# BEP32.net
KiCad netlist of a schematic drawn in EAGLE
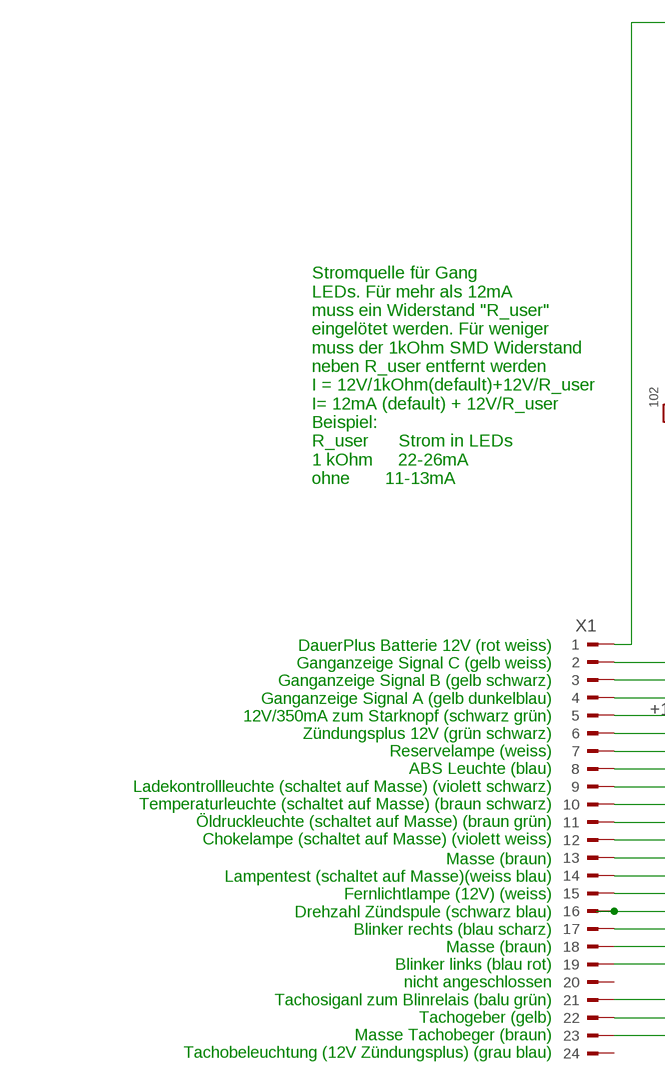
[diagram p0: schematic, sheet 1, part 1 of 2]
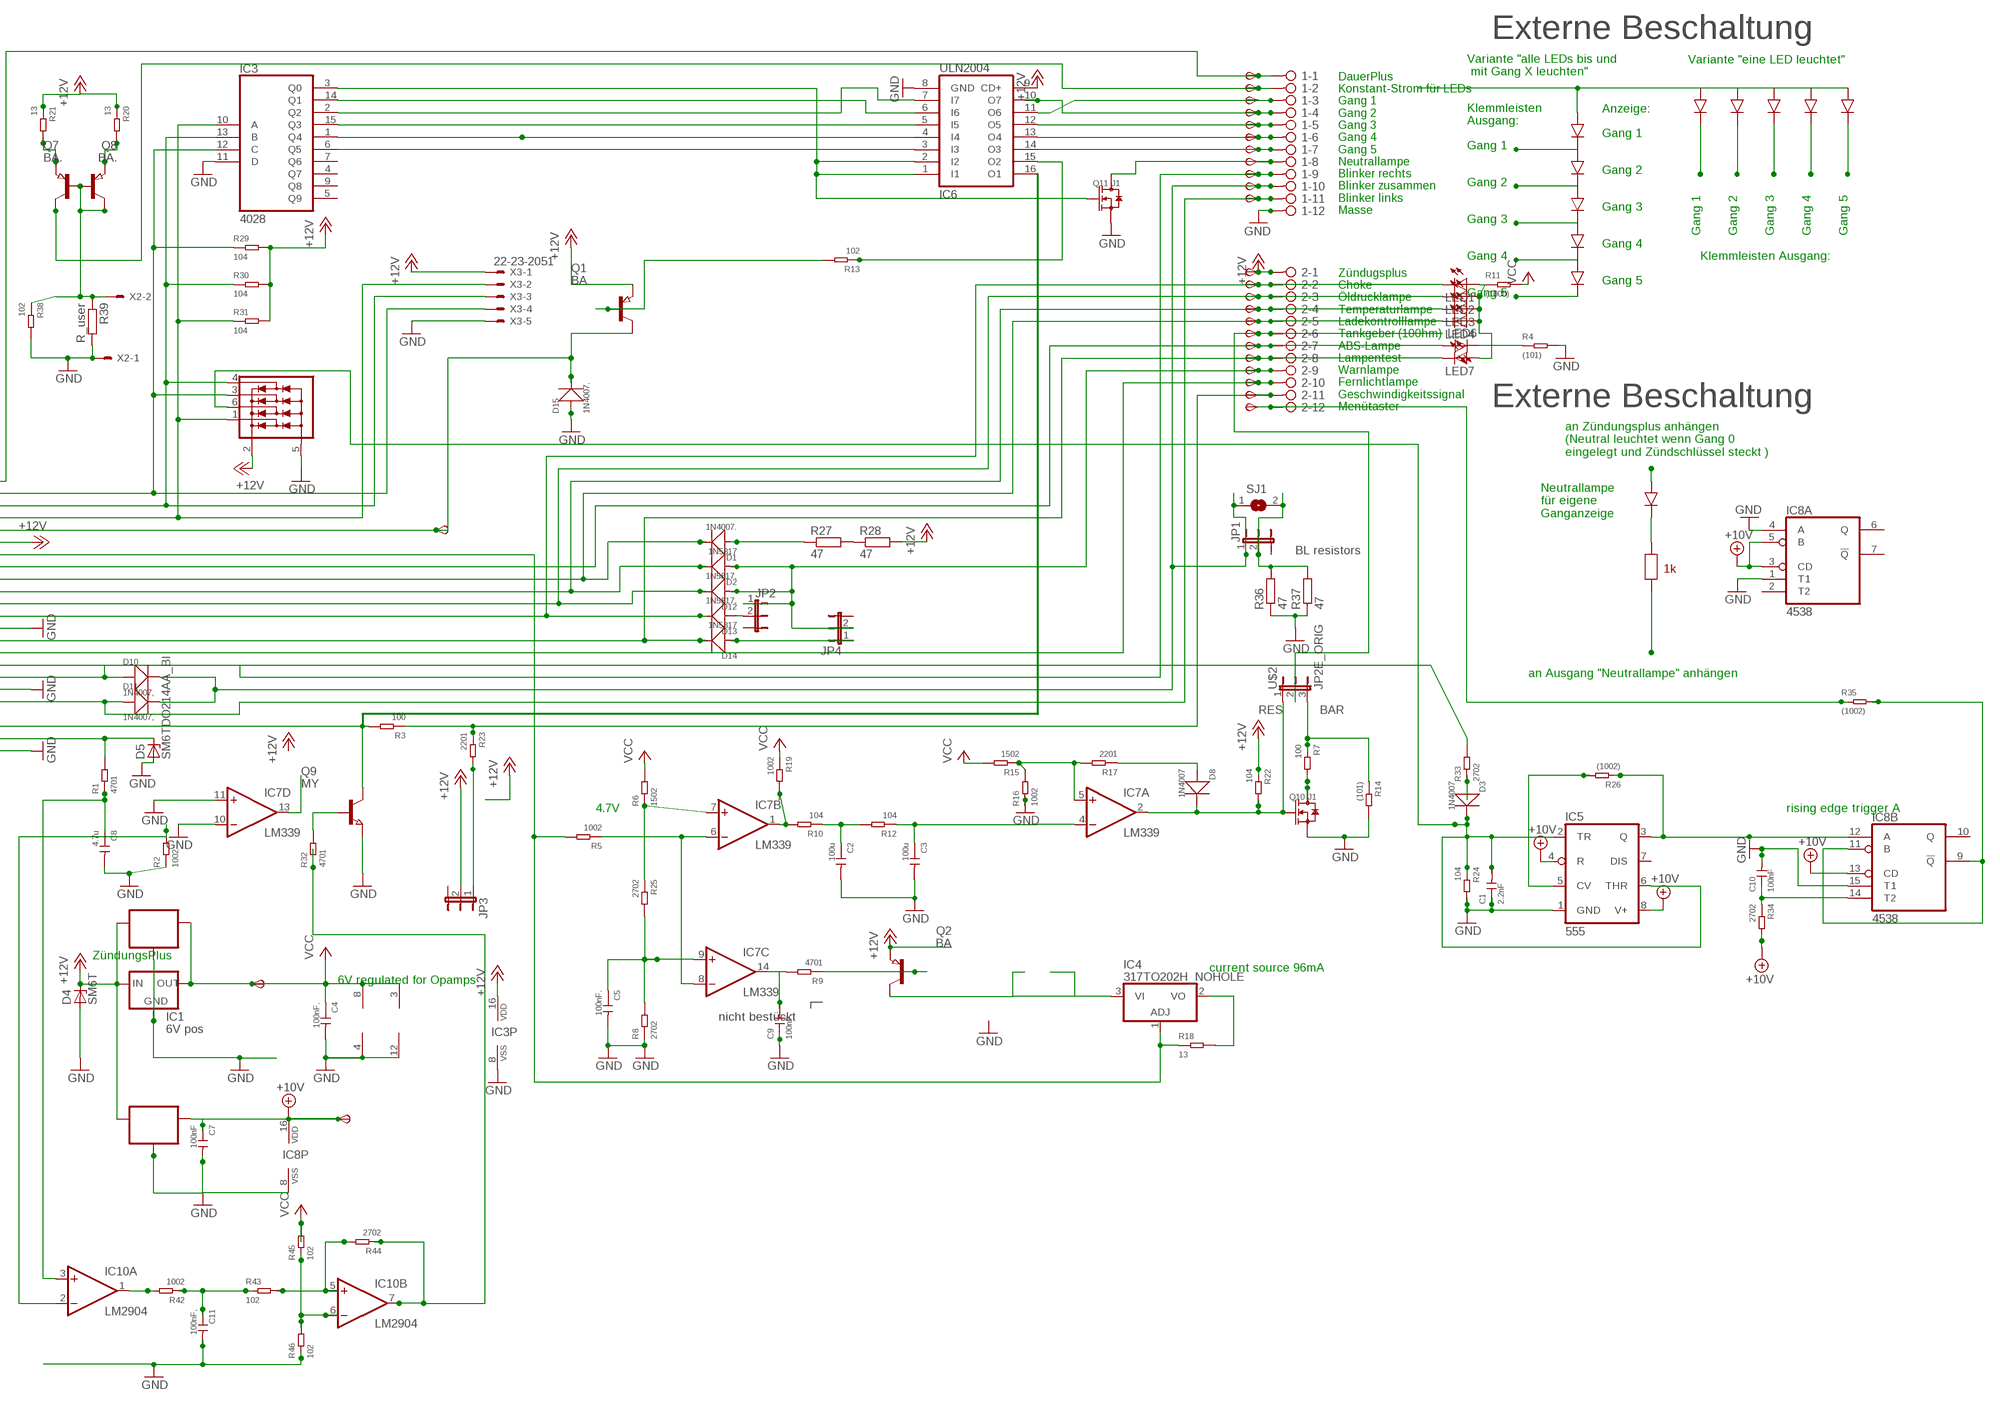
[diagram p1: schematic, sheet 1, part 2 of 2]

(export (version "E")
  (design (tool "Eeschema 10.0.6"))
  (components
    (comp (ref "1")
      (value "2081-1132")
      (footprint "eagle-import:12-PIN")
      (libsource (lib "eagle-import") (part "2081-1132"))
    )
    (comp (ref "2")
      (value "2081-1132")
      (footprint "eagle-import:12-PIN")
      (libsource (lib "eagle-import") (part "2081-1132"))
    )
    (comp (ref "6V")
      (value "TPSB2.0")
      (footprint "eagle-import:B2.0")
      (libsource (lib "eagle-import") (part "TPSB2.0"))
    )
    (comp (ref "10V")
      (value "TPSB2.0")
      (footprint "eagle-import:B2.0")
      (libsource (lib "eagle-import") (part "TPSB2.0"))
    )
    (comp (ref "C1")
      (value "2.2nF")
      (footprint "eagle-import:C0805")
      (fields (field (name "MPN") "CC0805KRX7R9BB104"))
      (libsource (lib "eagle-import") (part "CERAMIC-100NF-50V-10%-X7R(0805)"))
    )
    (comp (ref "C2")
      (value "100u")
      (footprint "eagle-import:C1206")
      (fields (field (name "MPN") "GRM31CR60J107ME39L"))
      (libsource (lib "eagle-import") (part "CERAMIC-100UF-6.3V-20%-X5R(1206)"))
    )
    (comp (ref "C3")
      (value "100u")
      (footprint "eagle-import:C1206")
      (fields (field (name "MPN") "GRM31CR60J107ME39L"))
      (libsource (lib "eagle-import") (part "CERAMIC-100UF-6.3V-20%-X5R(1206)"))
    )
    (comp (ref "C4")
      (value "100nF,")
      (footprint "eagle-import:C0805")
      (fields (field (name "MPN") "CC0805KRX7R9BB104"))
      (libsource (lib "eagle-import") (part "CERAMIC-100NF-50V-10%-X7R(0805)"))
    )
    (comp (ref "C5")
      (value "100nF.")
      (footprint "eagle-import:C0805")
      (fields (field (name "MPN") "CC0805KRX7R9BB104"))
      (libsource (lib "eagle-import") (part "CERAMIC-100NF-50V-10%-X7R(0805)"))
    )
    (comp (ref "C7")
      (value "100nF")
      (footprint "eagle-import:C0805")
      (fields (field (name "MPN") "CC0805KRX7R9BB104"))
      (libsource (lib "eagle-import") (part "CERAMIC-100NF-50V-10%-X7R(0805)"))
    )
    (comp (ref "C8")
      (value "4.7u")
      (footprint "eagle-import:C0805")
      (fields (field (name "MPN") "CC0805KKX5R8BB475"))
      (libsource (lib "eagle-import") (part "CERAMIC-4.7UF-25V-10%-X5R(0805)"))
    )
    (comp (ref "C9")
      (value "100nF.")
      (footprint "eagle-import:C0805")
      (fields (field (name "MPN") "CC0805KRX7R9BB104"))
      (libsource (lib "eagle-import") (part "CERAMIC-100NF-50V-10%-X7R(0805)"))
    )
    (comp (ref "C10")
      (value "100nF")
      (footprint "eagle-import:C0805")
      (fields (field (name "MPN") "CC0805KRX7R9BB104"))
      (libsource (lib "eagle-import") (part "CERAMIC-100NF-50V-10%-X7R(0805)"))
    )
    (comp (ref "C11")
      (value "100nF,")
      (footprint "eagle-import:C0805")
      (fields (field (name "MPN") "CC0805KRX7R9BB104"))
      (libsource (lib "eagle-import") (part "CERAMIC-100NF-50V-10%-X7R(0805)"))
    )
    (comp (ref "D1")
      (value "1N4007.")
      (footprint "eagle-import:DO-214AC")
      (fields (field (name "MPN") "1N4007"))
      (libsource (lib "eagle-import") (part "DIODE-GEN-PURPOSE-1KV-1A(DO-214AC)"))
    )
    (comp (ref "D2")
      (value "1N5817")
      (footprint "eagle-import:DO-214AC_SLIM")
      (libsource (lib "eagle-import") (part "DIODE-GEN-PURPOSE-1KV-1A(DO-214AC)DO-214AC/1206"))
    )
    (comp (ref "D3")
      (value "1N4007")
      (footprint "eagle-import:DO-214AC")
      (libsource (lib "eagle-import") (part "DIODE-GEN-PURPOSE-1KV-1A(DO-214AC)"))
    )
    (comp (ref "D4")
      (value "SM6T")
      (footprint "eagle-import:DO214AA")
      (libsource (lib "eagle-import") (part "SM6T"))
    )
    (comp (ref "D5")
      (value "SM6TDO214AA_BI")
      (footprint "eagle-import:DO214AA_BI")
      (libsource (lib "eagle-import") (part "SM6TDO214AA_BI"))
    )
    (comp (ref "D8")
      (value "1N4007")
      (footprint "eagle-import:DO-214AC")
      (libsource (lib "eagle-import") (part "DIODE-GEN-PURPOSE-1KV-1A(DO-214AC)"))
    )
    (comp (ref "D10")
      (value "1N4007,")
      (footprint "eagle-import:DO-214AC")
      (fields (field (name "MPN") "1N4007"))
      (libsource (lib "eagle-import") (part "DIODE-GEN-PURPOSE-1KV-1A(DO-214AC)"))
    )
    (comp (ref "D11")
      (value "1N4007,")
      (footprint "eagle-import:DO-214AC")
      (fields (field (name "MPN") "1N4007"))
      (libsource (lib "eagle-import") (part "DIODE-GEN-PURPOSE-1KV-1A(DO-214AC)"))
    )
    (comp (ref "D12")
      (value "1N5817.")
      (footprint "eagle-import:DO-214AC_SLIM")
      (libsource (lib "eagle-import") (part "DIODE-GEN-PURPOSE-1KV-1A(DO-214AC)DO-214AC/1206"))
    )
    (comp (ref "D13")
      (value "1N5817.")
      (footprint "eagle-import:DO-214AC_SLIM")
      (libsource (lib "eagle-import") (part "DIODE-GEN-PURPOSE-1KV-1A(DO-214AC)DO-214AC/1206"))
    )
    (comp (ref "D14")
      (value "1N5817")
      (footprint "eagle-import:DO-214AC_SLIM")
      (libsource (lib "eagle-import") (part "DIODE-GEN-PURPOSE-1KV-1A(DO-214AC)DO-214AC/1206"))
    )
    (comp (ref "D15")
      (value "1N4007.")
      (footprint "eagle-import:DO-214AC")
      (fields (field (name "MPN") "1N4007"))
      (libsource (lib "eagle-import") (part "DIODE-GEN-PURPOSE-1KV-1A(DO-214AC)"))
    )
    (comp (ref "IC1")
      (value "6V pos")
      (footprint "eagle-import:78LXX")
      (libsource (lib "eagle-import") (part "v-reg_78LXX"))
    )
    (comp (ref "IC2")
      (value "78L06")
      (footprint "eagle-import:SOT89_ROUND")
      (libsource (lib "eagle-import") (part "78LXXSOT89_ROUND"))
    )
    (comp (ref "IC3")
      (value "4028")
      (footprint "eagle-import:SO16")
      (libsource (lib "eagle-import") (part "4028D"))
    )
    (comp (ref "IC4")
      (value "317TO202H_NOHOLE")
      (footprint "eagle-import:TO220H_NOHOLE")
      (libsource (lib "eagle-import") (part "317TO202H_NOHOLE"))
    )
    (comp (ref "IC5")
      (value "555")
      (footprint "eagle-import:SO08")
      (libsource (lib "eagle-import") (part "555DNE"))
    )
    (comp (ref "IC6")
      (value "ULN2004")
      (footprint "eagle-import:SO16")
      (libsource (lib "eagle-import") (part "ULN2004AD"))
    )
    (comp (ref "IC7")
      (value "LM339")
      (footprint "eagle-import:SO14")
      (libsource (lib "eagle-import") (part "LM339D"))
    )
    (comp (ref "IC8")
      (value "4538")
      (footprint "eagle-import:SO16")
      (libsource (lib "eagle-import") (part "4538D"))
    )
    (comp (ref "IC9")
      (value "78L10")
      (footprint "eagle-import:SOT89_ROUND")
      (libsource (lib "eagle-import") (part "78LXXSOT89_ROUND"))
    )
    (comp (ref "IC10")
      (value "LM2904")
      (footprint "eagle-import:SO08")
      (libsource (lib "eagle-import") (part "LM358D"))
    )
    (comp (ref "JP1")
      (value "JP2EJP2_SMALLPADS")
      (footprint "eagle-import:JP2_SMALLPADS")
      (libsource (lib "eagle-import") (part "JP2EJP2_SMALLPADS"))
    )
    (comp (ref "JP2")
      (value "JP2EJP2_SMALLPADS")
      (footprint "eagle-import:JP2_SMALLPADS")
      (libsource (lib "eagle-import") (part "JP2EJP2_SMALLPADS"))
    )
    (comp (ref "JP3")
      (value "JP2EJP2_SMALLPADS")
      (footprint "eagle-import:JP2_SMALLPADS")
      (libsource (lib "eagle-import") (part "JP2EJP2_SMALLPADS"))
    )
    (comp (ref "JP4")
      (value "JP2EJP2_SMALLPADS")
      (footprint "eagle-import:JP2_SMALLPADS")
      (libsource (lib "eagle-import") (part "JP2EJP2_SMALLPADS"))
    )
    (comp (ref "LED1")
      (value "LEDLD260")
      (footprint "eagle-import:LD260")
      (libsource (lib "eagle-import") (part "LEDLD260"))
    )
    (comp (ref "LED2")
      (value "LEDLD260")
      (footprint "eagle-import:LD260")
      (libsource (lib "eagle-import") (part "LEDLD260"))
    )
    (comp (ref "LED3")
      (value "LEDLD260")
      (footprint "eagle-import:LD260")
      (libsource (lib "eagle-import") (part "LEDLD260"))
    )
    (comp (ref "LED4")
      (value "LEDLD260")
      (footprint "eagle-import:LD260")
      (libsource (lib "eagle-import") (part "LEDLD260"))
    )
    (comp (ref "LED6")
      (value "LEDLD260")
      (footprint "eagle-import:LD260")
      (libsource (lib "eagle-import") (part "LEDLD260"))
    )
    (comp (ref "LED7")
      (value "LEDLD260")
      (footprint "eagle-import:LD260")
      (libsource (lib "eagle-import") (part "LEDLD260"))
    )
    (comp (ref "Q1")
      (value "BA")
      (footprint "eagle-import:SOT89")
      (libsource (lib "eagle-import") (part "PNP-TRANSISTOR_SOT89"))
    )
    (comp (ref "Q2")
      (value "BA")
      (footprint "eagle-import:SOT89")
      (libsource (lib "eagle-import") (part "PNP-TRANSISTOR_SOT89"))
    )
    (comp (ref "Q7")
      (value "BA.")
      (footprint "eagle-import:SOT89")
      (libsource (lib "eagle-import") (part "PNP-TRANSISTOR_SOT89"))
    )
    (comp (ref "Q8")
      (value "BA.")
      (footprint "eagle-import:SOT89")
      (libsource (lib "eagle-import") (part "PNP-TRANSISTOR_SOT89"))
    )
    (comp (ref "Q9")
      (value "MY")
      (footprint "eagle-import:SOT89")
      (libsource (lib "eagle-import") (part "NPN-TRANSISTOR_SOT89"))
    )
    (comp (ref "Q10")
      (value "J1")
      (footprint "eagle-import:SOT-23")
      (fields (field (name "MPN") "BSS138W-7-F"))
      (libsource (lib "eagle-import") (part "SMD-MOSFET-N-CH-50V-200MA-BSS138W-7-F(SOT-23)"))
    )
    (comp (ref "Q11")
      (value "J1")
      (footprint "eagle-import:SOT-23")
      (fields (field (name "MPN") "BSS138W-7-F"))
      (libsource (lib "eagle-import") (part "SMD-MOSFET-N-CH-50V-200MA-BSS138W-7-F(SOT-23)"))
    )
    (comp (ref "R1")
      (value "4701")
      (footprint "eagle-import:R0805")
      (fields (field (name "MPN") "RC0805JR-074K7L"))
      (libsource (lib "eagle-import") (part "SMD-RES-4.7K-5%-1/8W(0805)"))
    )
    (comp (ref "R2")
      (value "1002")
      (footprint "eagle-import:R0805")
      (fields (field (name "MPN") "RC0805FR-0710KL"))
      (libsource (lib "eagle-import") (part "SMD-RES-10K-1%-1/8W(0805)"))
    )
    (comp (ref "R3")
      (value "100")
      (footprint "eagle-import:R0805")
      (fields (field (name "MPN") "RC0805JR-07220RL"))
      (libsource (lib "eagle-import") (part "SMD-RES-220R-5%-1/8W(0805)"))
    )
    (comp (ref "R4")
      (value "(101)")
      (footprint "eagle-import:R0805")
      (fields (field (name "MPN") "RC0805JR-07100RL"))
      (libsource (lib "eagle-import") (part "SMD-RES-100R-5%-1/8W(0805)"))
    )
    (comp (ref "R5")
      (value "1002")
      (footprint "eagle-import:R0805")
      (fields (field (name "MPN") "RC0805FR-0710KL"))
      (libsource (lib "eagle-import") (part "SMD-RES-10K-1%-1/8W(0805)"))
    )
    (comp (ref "R6")
      (value "1502")
      (footprint "eagle-import:R0805")
      (fields (field (name "MPN") "RC0805FR-0710KL"))
      (libsource (lib "eagle-import") (part "SMD-RES-10K-1%-1/8W(0805)"))
    )
    (comp (ref "R7")
      (value "100")
      (footprint "eagle-import:R0805")
      (fields (field (name "MPN") "RC0805JR-072K2L"))
      (libsource (lib "eagle-import") (part "SMD-RES-2.2K-5%-1/8W(0805)"))
    )
    (comp (ref "R8")
      (value "2702")
      (footprint "eagle-import:R0805")
      (fields (field (name "MPN") "RC0805JR-074K7L"))
      (libsource (lib "eagle-import") (part "SMD-RES-4.7K-5%-1/8W(0805)"))
    )
    (comp (ref "R9")
      (value "4701")
      (footprint "eagle-import:R0805")
      (fields (field (name "MPN") "RC0805JR-074K7L"))
      (libsource (lib "eagle-import") (part "SMD-RES-4.7K-5%-1/8W(0805)"))
    )
    (comp (ref "R10")
      (value "104")
      (footprint "eagle-import:R0805")
      (fields (field (name "MPN") "RC0805FR-0710KL"))
      (libsource (lib "eagle-import") (part "SMD-RES-10K-1%-1/8W(0805)"))
    )
    (comp (ref "R11")
      (value "(1000)")
      (footprint "eagle-import:R0805")
      (fields (field (name "MPN") "RC0805JR-07100RL"))
      (libsource (lib "eagle-import") (part "SMD-RES-100R-5%-1/8W(0805)"))
    )
    (comp (ref "R12")
      (value "104")
      (footprint "eagle-import:R0805")
      (fields (field (name "MPN") "RC0805FR-0710KL"))
      (libsource (lib "eagle-import") (part "SMD-RES-10K-1%-1/8W(0805)"))
    )
    (comp (ref "R13")
      (value "102")
      (footprint "eagle-import:R0805")
      (fields (field (name "MPN") "RC0805JR-071KL"))
      (libsource (lib "eagle-import") (part "SMD-RES-1K-5%-1/8W(0805)"))
    )
    (comp (ref "R14")
      (value "(101)")
      (footprint "eagle-import:R0805")
      (fields (field (name "MPN") "RC0805JR-072K2L"))
      (libsource (lib "eagle-import") (part "SMD-RES-2.2K-5%-1/8W(0805)"))
    )
    (comp (ref "R15")
      (value "1502")
      (footprint "eagle-import:R0805")
      (fields (field (name "MPN") "RC0805FR-0710KL"))
      (libsource (lib "eagle-import") (part "SMD-RES-10K-1%-1/8W(0805)"))
    )
    (comp (ref "R16")
      (value "1002")
      (footprint "eagle-import:R0805")
      (fields (field (name "MPN") "RC0805FR-0710KL"))
      (libsource (lib "eagle-import") (part "SMD-RES-10K-1%-1/8W(0805)"))
    )
    (comp (ref "R17")
      (value "2201")
      (footprint "eagle-import:R0805")
      (fields (field (name "MPN") "RC0805JR-072K2L"))
      (libsource (lib "eagle-import") (part "SMD-RES-2.2K-5%-1/8W(0805)"))
    )
    (comp (ref "R18")
      (value "13")
      (footprint "eagle-import:R1206")
      (fields (field (name "MPN") "RC1206JR-0713RL"))
      (libsource (lib "eagle-import") (part "SMD-RES-13R-5%-1/4W(1206)"))
    )
    (comp (ref "R19")
      (value "1002")
      (footprint "eagle-import:R0805")
      (fields (field (name "MPN") "RC0805FR-0710KL"))
      (libsource (lib "eagle-import") (part "SMD-RES-10K-1%-1/8W(0805)"))
    )
    (comp (ref "R20")
      (value "13")
      (footprint "eagle-import:R1206")
      (fields (field (name "MPN") "RC1206JR-0713RL"))
      (libsource (lib "eagle-import") (part "SMD-RES-13R-5%-1/4W(1206)"))
    )
    (comp (ref "R21")
      (value "13")
      (footprint "eagle-import:R1206")
      (fields (field (name "MPN") "RC1206JR-0713RL"))
      (libsource (lib "eagle-import") (part "SMD-RES-13R-5%-1/4W(1206)"))
    )
    (comp (ref "R22")
      (value "104")
      (footprint "eagle-import:R0805")
      (fields (field (name "MPN") "RC0805FR-0710KL"))
      (libsource (lib "eagle-import") (part "SMD-RES-10K-1%-1/8W(0805)"))
    )
    (comp (ref "R23")
      (value "2201")
      (footprint "eagle-import:R0805")
      (fields (field (name "MPN") "RC0805JR-072K2L"))
      (libsource (lib "eagle-import") (part "SMD-RES-2.2K-5%-1/8W(0805)"))
    )
    (comp (ref "R24")
      (value "104")
      (footprint "eagle-import:R0805")
      (fields (field (name "MPN") "RC0805FR-0710KL"))
      (libsource (lib "eagle-import") (part "SMD-RES-10K-1%-1/8W(0805)"))
    )
    (comp (ref "R25")
      (value "2702")
      (footprint "eagle-import:R0805")
      (fields (field (name "MPN") "RC0805JR-074K7L"))
      (libsource (lib "eagle-import") (part "SMD-RES-4.7K-5%-1/8W(0805)"))
    )
    (comp (ref "R26")
      (value "(1002)")
      (footprint "eagle-import:R0805")
      (fields (field (name "MPN") "RC0805FR-0710KL"))
      (libsource (lib "eagle-import") (part "SMD-RES-10K-1%-1/8W(0805)"))
    )
    (comp (ref "R27")
      (value "47")
      (footprint "eagle-import:V235_17_1MM")
      (libsource (lib "eagle-import") (part "R-EU_V235/17_1MM"))
    )
    (comp (ref "R28")
      (value "47")
      (footprint "eagle-import:V235_17_1MM")
      (libsource (lib "eagle-import") (part "R-EU_V235/17_1MM"))
    )
    (comp (ref "R29")
      (value "104")
      (footprint "eagle-import:R0805")
      (fields (field (name "MPN") "RC0805FR-0710KL"))
      (libsource (lib "eagle-import") (part "SMD-RES-10K-1%-1/8W(0805)"))
    )
    (comp (ref "R30")
      (value "104")
      (footprint "eagle-import:R0805")
      (fields (field (name "MPN") "RC0805FR-0710KL"))
      (libsource (lib "eagle-import") (part "SMD-RES-10K-1%-1/8W(0805)"))
    )
    (comp (ref "R31")
      (value "104")
      (footprint "eagle-import:R0805")
      (fields (field (name "MPN") "RC0805FR-0710KL"))
      (libsource (lib "eagle-import") (part "SMD-RES-10K-1%-1/8W(0805)"))
    )
    (comp (ref "R32")
      (value "4701")
      (footprint "eagle-import:R0805")
      (fields (field (name "MPN") "RC0805JR-074K7L"))
      (libsource (lib "eagle-import") (part "SMD-RES-4.7K-5%-1/8W(0805)"))
    )
    (comp (ref "R33")
      (value "2702")
      (footprint "eagle-import:R0805")
      (fields (field (name "MPN") "RC0805FR-0710KL"))
      (libsource (lib "eagle-import") (part "SMD-RES-10K-1%-1/8W(0805)"))
    )
    (comp (ref "R34")
      (value "2702")
      (footprint "eagle-import:R0805")
      (fields (field (name "MPN") "RC0805JR-074K7L"))
      (libsource (lib "eagle-import") (part "SMD-RES-4.7K-5%-1/8W(0805)"))
    )
    (comp (ref "R35")
      (value "(1002)")
      (footprint "eagle-import:R0805")
      (fields (field (name "MPN") "RC0805JR-074K7L"))
      (libsource (lib "eagle-import") (part "SMD-RES-4.7K-5%-1/8W(0805)"))
    )
    (comp (ref "R36")
      (value "47")
      (footprint "eagle-import:V235_17_1MM")
      (libsource (lib "eagle-import") (part "R-EU_V235/17_1MM"))
    )
    (comp (ref "R37")
      (value "47")
      (footprint "eagle-import:V235_17_1MM")
      (libsource (lib "eagle-import") (part "R-EU_V235/17_1MM"))
    )
    (comp (ref "R38")
      (value "102")
      (footprint "eagle-import:R0805")
      (fields (field (name "MPN") "RC0805JR-071KL"))
      (libsource (lib "eagle-import") (part "SMD-RES-1K-5%-1/8W(0805)"))
    )
    (comp (ref "R39")
      (value "R_user")
      (footprint "eagle-import:R0805")
      (libsource (lib "eagle-import") (part "R-EU_R0805"))
    )
    (comp (ref "R42")
      (value "1002")
      (footprint "eagle-import:R0805")
      (fields (field (name "MPN") "RC0805FR-0710KL"))
      (libsource (lib "eagle-import") (part "SMD-RES-10K-1%-1/8W(0805)"))
    )
    (comp (ref "R43")
      (value "102")
      (footprint "eagle-import:R0805")
      (fields (field (name "MPN") "RC0805JR-071KL"))
      (libsource (lib "eagle-import") (part "SMD-RES-1K-5%-1/8W(0805)"))
    )
    (comp (ref "R44")
      (value "2702")
      (footprint "eagle-import:R0805")
      (fields (field (name "MPN") "RC0805JR-074K7L"))
      (libsource (lib "eagle-import") (part "SMD-RES-4.7K-5%-1/8W(0805)"))
    )
    (comp (ref "R45")
      (value "102")
      (footprint "eagle-import:R0805")
      (fields (field (name "MPN") "RC0805JR-071KL"))
      (libsource (lib "eagle-import") (part "SMD-RES-1K-5%-1/8W(0805)"))
    )
    (comp (ref "R46")
      (value "102")
      (footprint "eagle-import:R0805")
      (fields (field (name "MPN") "RC0805JR-071KL"))
      (libsource (lib "eagle-import") (part "SMD-RES-1K-5%-1/8W(0805)"))
    )
    (comp (ref "SJ1") (value "SJ") (footprint "eagle-import:SJ") (libsource (lib "eagle-import") (part "SJ")))
    (comp (ref "START")
      (value "TPSB2.0")
      (footprint "eagle-import:B2.0")
      (libsource (lib "eagle-import") (part "TPSB2.0"))
    )
    (comp (ref "TP1")
      (value "TPSB2.0")
      (footprint "eagle-import:B2.0")
      (libsource (lib "eagle-import") (part "TPSB2.0"))
    )
    (comp (ref "TP2")
      (value "TPSB2.0")
      (footprint "eagle-import:B2.0")
      (libsource (lib "eagle-import") (part "TPSB2.0"))
    )
    (comp (ref "TP3")
      (value "TPSB2.0")
      (footprint "eagle-import:B2.0")
      (libsource (lib "eagle-import") (part "TPSB2.0"))
    )
    (comp (ref "TP4")
      (value "TPSB2.0")
      (footprint "eagle-import:B2.0")
      (libsource (lib "eagle-import") (part "TPSB2.0"))
    )
    (comp (ref "TP5")
      (value "TPSB2.0")
      (footprint "eagle-import:B2.0")
      (libsource (lib "eagle-import") (part "TPSB2.0"))
    )
    (comp (ref "TP6")
      (value "TPSB2.0")
      (footprint "eagle-import:B2.0")
      (libsource (lib "eagle-import") (part "TPSB2.0"))
    )
    (comp (ref "TP7")
      (value "TPSB2.0")
      (footprint "eagle-import:B2.0")
      (libsource (lib "eagle-import") (part "TPSB2.0"))
    )
    (comp (ref "TP8")
      (value "TPSB2.0")
      (footprint "eagle-import:B2.0")
      (libsource (lib "eagle-import") (part "TPSB2.0"))
    )
    (comp (ref "TP9")
      (value "TPSB2.0")
      (footprint "eagle-import:B2.0")
      (libsource (lib "eagle-import") (part "TPSB2.0"))
    )
    (comp (ref "TP10")
      (value "TPSB2.0")
      (footprint "eagle-import:B2.0")
      (libsource (lib "eagle-import") (part "TPSB2.0"))
    )
    (comp (ref "TP11")
      (value "TPSB2.0")
      (footprint "eagle-import:B2.0")
      (libsource (lib "eagle-import") (part "TPSB2.0"))
    )
    (comp (ref "TP12")
      (value "TPSB2.0")
      (footprint "eagle-import:B2.0")
      (libsource (lib "eagle-import") (part "TPSB2.0"))
    )
    (comp (ref "TP13")
      (value "TPSB2.0")
      (footprint "eagle-import:B2.0")
      (libsource (lib "eagle-import") (part "TPSB2.0"))
    )
    (comp (ref "TP16")
      (value "TPSB2.0")
      (footprint "eagle-import:B2.0")
      (libsource (lib "eagle-import") (part "TPSB2.0"))
    )
    (comp (ref "TP17")
      (value "TPSB2.0")
      (footprint "eagle-import:B2.0")
      (libsource (lib "eagle-import") (part "TPSB2.0"))
    )
    (comp (ref "TP18")
      (value "TPSB2.0")
      (footprint "eagle-import:B2.0")
      (libsource (lib "eagle-import") (part "TPSB2.0"))
    )
    (comp (ref "TP19")
      (value "TPSB2.0")
      (footprint "eagle-import:B2.0")
      (libsource (lib "eagle-import") (part "TPSB2.0"))
    )
    (comp (ref "TP21")
      (value "TPSB2.0")
      (footprint "eagle-import:B2.0")
      (libsource (lib "eagle-import") (part "TPSB2.0"))
    )
    (comp (ref "TP22")
      (value "TPSB2.0")
      (footprint "eagle-import:B2.0")
      (libsource (lib "eagle-import") (part "TPSB2.0"))
    )
    (comp (ref "TP23")
      (value "TPSB2.0")
      (footprint "eagle-import:B2.0")
      (libsource (lib "eagle-import") (part "TPSB2.0"))
    )
    (comp (ref "TP24")
      (value "TPSB1,27")
      (footprint "eagle-import:B1,27")
      (libsource (lib "eagle-import") (part "TPSB1,27"))
    )
    (comp (ref "TP25")
      (value "TPSB2.0")
      (footprint "eagle-import:B2.0")
      (libsource (lib "eagle-import") (part "TPSB2.0"))
    )
    (comp (ref "TP26")
      (value "TPSB2.0")
      (footprint "eagle-import:B2.0")
      (libsource (lib "eagle-import") (part "TPSB2.0"))
    )
    (comp (ref "U$2")
      (value "JP2E_ORIG")
      (footprint "eagle-import:JP2_ORIG_SMALLPADS")
      (libsource (lib "eagle-import") (part "JP2E_ORIG"))
    )
    (comp (ref "U$3")
      (value "NUP4304SOT457_R")
      (footprint "eagle-import:SOT457R_PHILIPS")
      (libsource (lib "eagle-import") (part "NUP4304SOT457_R"))
    )
    (comp (ref "X1")
      (value "CON_BMWV2")
      (footprint "eagle-import:24-PIN_V2")
      (libsource (lib "eagle-import") (part "CON_BMWV2"))
    )
    (comp (ref "X2")
      (value "22-23-2021")
      (footprint "eagle-import:22-23-2021")
      (fields (field (name "MF") "MOLEX"))
      (libsource (lib "eagle-import") (part "22-23-2021"))
    )
    (comp (ref "X3")
      (value "22-23-2051")
      (footprint "eagle-import:22-23-2051")
      (fields (field (name "MF") "MOLEX"))
      (libsource (lib "eagle-import") (part "22-23-2051"))
    )
  )
  (nets
    (net (code "1") (name "+10V") (class "Default")
      (node (ref "10V") (pin "TP") (pinfunction "PP_TP") (pintype "input"))
      (node (ref "C7") (pin "1") (pinfunction "1_1") (pintype "passive"))
      (node (ref "IC5") (pin "4") (pinfunction "R_4") (pintype "input"))
      (node (ref "IC5") (pin "8") (pinfunction "V+_8") (pintype "power_in"))
      (node (ref "IC8") (pin "13") (pinfunction "CD_13") (pintype "input"))
      (node (ref "IC8") (pin "16") (pinfunction "VDD_16") (pintype "power_in"))
      (node (ref "IC8") (pin "3") (pinfunction "CD_3") (pintype "input"))
      (node (ref "IC8") (pin "5") (pinfunction "B_5") (pintype "input"))
      (node (ref "IC9") (pin "1") (pinfunction "OUT_1") (pintype "passive"))
      (node (ref "R34") (pin "2") (pinfunction "2_2") (pintype "passive"))
    )
    (net (code "2") (name "+12V") (class "Default")
      (node (ref "2") (pin "1") (pinfunction "KL_1") (pintype "passive"))
      (node (ref "D4") (pin "C") (pinfunction "C_C") (pintype "passive"))
      (node (ref "IC1") (pin "IN") (pinfunction "IN_IN") (pintype "input"))
      (node (ref "IC2") (pin "3") (pinfunction "IN_3") (pintype "input"))
      (node (ref "IC3") (pin "16") (pinfunction "VDD_16") (pintype "power_in"))
      (node (ref "IC6") (pin "9") (pinfunction "CD+_9") (pintype "passive"))
      (node (ref "IC9") (pin "3") (pinfunction "IN_3") (pintype "input"))
      (node (ref "JP3") (pin "2") (pinfunction "2_2") (pintype "passive"))
      (node (ref "Q1") (pin "3") (pinfunction "E_3") (pintype "passive"))
      (node (ref "Q2") (pin "3") (pinfunction "E_3") (pintype "passive"))
      (node (ref "R20") (pin "1") (pinfunction "1_1") (pintype "passive"))
      (node (ref "R21") (pin "1") (pinfunction "1_1") (pintype "passive"))
      (node (ref "R22") (pin "1") (pinfunction "1_1") (pintype "passive"))
      (node (ref "R28") (pin "2") (pinfunction "2_2") (pintype "passive"))
      (node (ref "R29") (pin "2") (pinfunction "2_2") (pintype "passive"))
      (node (ref "R30") (pin "2") (pinfunction "2_2") (pintype "passive"))
      (node (ref "R31") (pin "2") (pinfunction "2_2") (pintype "passive"))
      (node (ref "TP12") (pin "TP") (pinfunction "PP_TP") (pintype "input"))
      (node (ref "U$3") (pin "2") (pinfunction "V+_2") (pintype "passive"))
      (node (ref "X1") (pin "6") (pinfunction "6_6") (pintype "passive"))
      (node (ref "X3") (pin "1") (pinfunction "S_1") (pintype "passive"))
    )
    (net (code "3") (name "GND") (class "Default")
      (node (ref "1") (pin "12") (pinfunction "KL_12") (pintype "passive"))
      (node (ref "C1") (pin "1") (pinfunction "1_1") (pintype "passive"))
      (node (ref "C10") (pin "2") (pinfunction "2_2") (pintype "passive"))
      (node (ref "C11") (pin "2") (pinfunction "2_2") (pintype "passive"))
      (node (ref "C2") (pin "2") (pinfunction "2_2") (pintype "passive"))
      (node (ref "C3") (pin "2") (pinfunction "2_2") (pintype "passive"))
      (node (ref "C4") (pin "2") (pinfunction "2_2") (pintype "passive"))
      (node (ref "C5") (pin "2") (pinfunction "2_2") (pintype "passive"))
      (node (ref "C7") (pin "2") (pinfunction "2_2") (pintype "passive"))
      (node (ref "C8") (pin "2") (pinfunction "2_2") (pintype "passive"))
      (node (ref "C9") (pin "1") (pinfunction "1_1") (pintype "passive"))
      (node (ref "D15") (pin "1") (pinfunction "+_1") (pintype "passive"))
      (node (ref "D4") (pin "A") (pinfunction "A_A") (pintype "passive"))
      (node (ref "D5") (pin "A") (pinfunction "A_A") (pintype "passive"))
      (node (ref "IC1") (pin "GND") (pinfunction "GND_GND") (pintype "input"))
      (node (ref "IC10") (pin "4") (pinfunction "V-_4") (pintype "power_in"))
      (node (ref "IC2") (pin "2") (pinfunction "GND_2") (pintype "input"))
      (node (ref "IC2") (pin "2@1") (pinfunction "GND_2@1") (pintype "input"))
      (node (ref "IC3") (pin "11") (pinfunction "D_11") (pintype "input"))
      (node (ref "IC3") (pin "8") (pinfunction "VSS_8") (pintype "power_in"))
      (node (ref "IC5") (pin "1") (pinfunction "GND_1") (pintype "power_in"))
      (node (ref "IC6") (pin "8") (pinfunction "GND_8") (pintype "power_in"))
      (node (ref "IC7") (pin "10") (pinfunction "-IN_10") (pintype "input"))
      (node (ref "IC7") (pin "11") (pinfunction "+IN_11") (pintype "input"))
      (node (ref "IC7") (pin "12") (pinfunction "GND_12") (pintype "power_in"))
      (node (ref "IC8") (pin "1") (pinfunction "T1_1") (pintype "input"))
      (node (ref "IC8") (pin "15") (pinfunction "T1_15") (pintype "input"))
      (node (ref "IC8") (pin "4") (pinfunction "A_4") (pintype "input"))
      (node (ref "IC8") (pin "8") (pinfunction "VSS_8") (pintype "power_in"))
      (node (ref "IC9") (pin "2") (pinfunction "GND_2") (pintype "input"))
      (node (ref "IC9") (pin "2@1") (pinfunction "GND_2@1") (pintype "input"))
      (node (ref "Q10") (pin "2") (pinfunction "S_2") (pintype "passive"))
      (node (ref "Q11") (pin "2") (pinfunction "S_2") (pintype "passive"))
      (node (ref "Q9") (pin "3") (pinfunction "E_3") (pintype "passive"))
      (node (ref "R14") (pin "2") (pinfunction "2_2") (pintype "passive"))
      (node (ref "R16") (pin "1") (pinfunction "1_1") (pintype "passive"))
      (node (ref "R2") (pin "1") (pinfunction "1_1") (pintype "passive"))
      (node (ref "R24") (pin "2") (pinfunction "2_2") (pintype "passive"))
      (node (ref "R36") (pin "1") (pinfunction "1_1") (pintype "passive"))
      (node (ref "R37") (pin "1") (pinfunction "1_1") (pintype "passive"))
      (node (ref "R38") (pin "2") (pinfunction "2_2") (pintype "passive"))
      (node (ref "R39") (pin "2") (pinfunction "2_2") (pintype "passive"))
      (node (ref "R4") (pin "2") (pinfunction "2_2") (pintype "passive"))
      (node (ref "R46") (pin "1") (pinfunction "1_1") (pintype "passive"))
      (node (ref "R8") (pin "1") (pinfunction "1_1") (pintype "passive"))
      (node (ref "U$3") (pin "5") (pinfunction "V-_5") (pintype "passive"))
      (node (ref "X1") (pin "13") (pinfunction "13_13") (pintype "passive"))
      (node (ref "X1") (pin "18") (pinfunction "18_18") (pintype "passive"))
      (node (ref "X1") (pin "23") (pinfunction "23_23") (pintype "passive"))
      (node (ref "X2") (pin "1") (pinfunction "S_1") (pintype "passive"))
      (node (ref "X3") (pin "5") (pinfunction "S_5") (pintype "passive"))
    )
    (net (code "4") (name "Net-(1A-KL)") (class "Default")
      (node (ref "1") (pin "1") (pinfunction "KL_1") (pintype "passive"))
      (node (ref "TP1") (pin "TP") (pinfunction "PP_TP") (pintype "input"))
      (node (ref "X1") (pin "1") (pinfunction "1_1") (pintype "passive"))
    )
    (net (code "5") (name "Net-(1B-KL)") (class "Default")
      (node (ref "1") (pin "10") (pinfunction "KL_10") (pintype "passive"))
      (node (ref "D10") (pin "2") (pinfunction "-_2") (pintype "passive"))
      (node (ref "D11") (pin "2") (pinfunction "-_2") (pintype "passive"))
      (node (ref "JP1") (pin "1") (pinfunction "1_1") (pintype "passive"))
      (node (ref "SJ1") (pin "1") (pinfunction "1_1") (pintype "passive"))
      (node (ref "TP10") (pin "TP") (pinfunction "PP_TP") (pintype "input"))
    )
    (net (code "6") (name "Net-(1C-KL)") (class "Default")
      (node (ref "1") (pin "11") (pinfunction "KL_11") (pintype "passive"))
      (node (ref "D11") (pin "1") (pinfunction "+_1") (pintype "passive"))
      (node (ref "TP11") (pin "TP") (pinfunction "PP_TP") (pintype "input"))
      (node (ref "X1") (pin "19") (pinfunction "19_19") (pintype "passive"))
    )
    (net (code "7") (name "Net-(1E-KL)") (class "Default")
      (node (ref "1") (pin "2") (pinfunction "KL_2") (pintype "passive"))
      (node (ref "Q8") (pin "2") (pinfunction "C_2") (pintype "passive"))
      (node (ref "TP2") (pin "TP") (pinfunction "PP_TP") (pintype "input"))
    )
    (net (code "8") (name "Net-(1F-KL)") (class "Default")
      (node (ref "1") (pin "3") (pinfunction "KL_3") (pintype "passive"))
      (node (ref "IC6") (pin "11") (pinfunction "O6_11") (pintype "open_collector"))
      (node (ref "TP3") (pin "TP") (pinfunction "PP_TP") (pintype "input"))
    )
    (net (code "9") (name "Net-(1G-KL)") (class "Default")
      (node (ref "1") (pin "4") (pinfunction "KL_4") (pintype "passive"))
      (node (ref "IC6") (pin "10") (pinfunction "O7_10") (pintype "open_collector"))
      (node (ref "TP4") (pin "TP") (pinfunction "PP_TP") (pintype "input"))
    )
    (net (code "10") (name "Net-(1H-KL)") (class "Default")
      (node (ref "1") (pin "5") (pinfunction "KL_5") (pintype "passive"))
      (node (ref "IC6") (pin "12") (pinfunction "O5_12") (pintype "open_collector"))
      (node (ref "TP5") (pin "TP") (pinfunction "PP_TP") (pintype "input"))
    )
    (net (code "11") (name "Net-(1I-KL)") (class "Default")
      (node (ref "1") (pin "6") (pinfunction "KL_6") (pintype "passive"))
      (node (ref "IC6") (pin "13") (pinfunction "O4_13") (pintype "open_collector"))
      (node (ref "TP6") (pin "TP") (pinfunction "PP_TP") (pintype "input"))
    )
    (net (code "12") (name "Net-(1J-KL)") (class "Default")
      (node (ref "1") (pin "7") (pinfunction "KL_7") (pintype "passive"))
      (node (ref "IC6") (pin "14") (pinfunction "O3_14") (pintype "open_collector"))
      (node (ref "TP7") (pin "TP") (pinfunction "PP_TP") (pintype "input"))
    )
    (net (code "13") (name "Net-(1K-KL)") (class "Default")
      (node (ref "1") (pin "8") (pinfunction "KL_8") (pintype "passive"))
      (node (ref "Q11") (pin "3") (pinfunction "D_3") (pintype "passive"))
      (node (ref "TP8") (pin "TP") (pinfunction "PP_TP") (pintype "input"))
    )
    (net (code "14") (name "Net-(1L-KL)") (class "Default")
      (node (ref "1") (pin "9") (pinfunction "KL_9") (pintype "passive"))
      (node (ref "D10") (pin "1") (pinfunction "+_1") (pintype "passive"))
      (node (ref "TP9") (pin "TP") (pinfunction "PP_TP") (pintype "input"))
      (node (ref "X1") (pin "17") (pinfunction "17_17") (pintype "passive"))
    )
    (net (code "15") (name "Net-(2B-KL)") (class "Default")
      (node (ref "2") (pin "10") (pinfunction "KL_10") (pintype "passive"))
      (node (ref "TP25") (pin "TP") (pinfunction "PP_TP") (pintype "input"))
      (node (ref "X1") (pin "15") (pinfunction "15_15") (pintype "passive"))
    )
    (net (code "16") (name "Net-(2C-KL)") (class "Default")
      (node (ref "2") (pin "11") (pinfunction "KL_11") (pintype "passive"))
      (node (ref "R23") (pin "1") (pinfunction "1_1") (pintype "passive"))
      (node (ref "R3") (pin "1") (pinfunction "1_1") (pintype "passive"))
      (node (ref "TP26") (pin "TP") (pinfunction "PP_TP") (pintype "input"))
    )
    (net (code "17") (name "Net-(2D-KL)") (class "Default")
      (node (ref "2") (pin "12") (pinfunction "KL_12") (pintype "passive"))
      (node (ref "R35") (pin "1") (pinfunction "1_1") (pintype "passive"))
      (node (ref "TP13") (pin "TP") (pinfunction "PP_TP") (pintype "input"))
    )
    (net (code "18") (name "Net-(2E-KL)") (class "Default")
      (node (ref "2") (pin "2") (pinfunction "KL_2") (pintype "passive"))
      (node (ref "D13") (pin "2") (pinfunction "-_2") (pintype "passive"))
      (node (ref "LED1") (pin "K") (pinfunction "C_K") (pintype "passive"))
      (node (ref "TP16") (pin "TP") (pinfunction "PP_TP") (pintype "input"))
      (node (ref "X1") (pin "12") (pinfunction "12_12") (pintype "passive"))
    )
    (net (code "19") (name "Net-(2F-KL)") (class "Default")
      (node (ref "2") (pin "3") (pinfunction "KL_3") (pintype "passive"))
      (node (ref "D12") (pin "2") (pinfunction "-_2") (pintype "passive"))
      (node (ref "LED2") (pin "K") (pinfunction "C_K") (pintype "passive"))
      (node (ref "TP17") (pin "TP") (pinfunction "PP_TP") (pintype "input"))
      (node (ref "X1") (pin "11") (pinfunction "11_11") (pintype "passive"))
    )
    (net (code "20") (name "Net-(2G-KL)") (class "Default")
      (node (ref "2") (pin "4") (pinfunction "KL_4") (pintype "passive"))
      (node (ref "D2") (pin "2") (pinfunction "-_2") (pintype "passive"))
      (node (ref "LED3") (pin "K") (pinfunction "C_K") (pintype "passive"))
      (node (ref "TP18") (pin "TP") (pinfunction "PP_TP") (pintype "input"))
      (node (ref "X1") (pin "10") (pinfunction "10_10") (pintype "passive"))
    )
    (net (code "21") (name "Net-(2H-KL)") (class "Default")
      (node (ref "2") (pin "5") (pinfunction "KL_5") (pintype "passive"))
      (node (ref "D1") (pin "2") (pinfunction "-_2") (pintype "passive"))
      (node (ref "LED4") (pin "K") (pinfunction "C_K") (pintype "passive"))
      (node (ref "TP19") (pin "TP") (pinfunction "PP_TP") (pintype "input"))
      (node (ref "X1") (pin "9") (pinfunction "9_9") (pintype "passive"))
    )
    (net (code "22") (name "Net-(2I-KL)") (class "Default")
      (node (ref "2") (pin "6") (pinfunction "KL_6") (pintype "passive"))
      (node (ref "TP21") (pin "TP") (pinfunction "PP_TP") (pintype "input"))
      (node (ref "U$2") (pin "2") (pinfunction "2_2") (pintype "passive"))
    )
    (net (code "23") (name "Net-(2J-KL)") (class "Default")
      (node (ref "2") (pin "7") (pinfunction "KL_7") (pintype "passive"))
      (node (ref "LED6") (pin "A") (pinfunction "A_A") (pintype "passive"))
      (node (ref "TP22") (pin "TP") (pinfunction "PP_TP") (pintype "input"))
      (node (ref "X1") (pin "8") (pinfunction "8_8") (pintype "passive"))
    )
    (net (code "24") (name "Net-(2K-KL)") (class "Default")
      (node (ref "2") (pin "8") (pinfunction "KL_8") (pintype "passive"))
      (node (ref "D14") (pin "2") (pinfunction "-_2") (pintype "passive"))
      (node (ref "LED7") (pin "K") (pinfunction "C_K") (pintype "passive"))
      (node (ref "TP23") (pin "TP") (pinfunction "PP_TP") (pintype "input"))
      (node (ref "X1") (pin "14") (pinfunction "14_14") (pintype "passive"))
    )
    (net (code "25") (name "Net-(2L-KL)") (class "Default")
      (node (ref "2") (pin "9") (pinfunction "KL_9") (pintype "passive"))
      (node (ref "D12") (pin "1") (pinfunction "+_1") (pintype "passive"))
      (node (ref "D2") (pin "1") (pinfunction "+_1") (pintype "passive"))
      (node (ref "JP2") (pin "1") (pinfunction "1_1") (pintype "passive"))
      (node (ref "JP4") (pin "2") (pinfunction "2_2") (pintype "passive"))
      (node (ref "TP24") (pin "TP") (pinfunction "PP_TP") (pintype "input"))
    )
    (net (code "26") (name "Net-(C2-Pad1)") (class "Default")
      (node (ref "C2") (pin "1") (pinfunction "1_1") (pintype "passive"))
      (node (ref "R10") (pin "1") (pinfunction "1_1") (pintype "passive"))
      (node (ref "R12") (pin "2") (pinfunction "2_2") (pintype "passive"))
    )
    (net (code "27") (name "Net-(C11-Pad1)") (class "Default")
      (node (ref "C11") (pin "1") (pinfunction "1_1") (pintype "passive"))
      (node (ref "R42") (pin "1") (pinfunction "1_1") (pintype "passive"))
      (node (ref "R43") (pin "1") (pinfunction "1_1") (pintype "passive"))
    )
    (net (code "28") (name "Net-(D1-+)") (class "Default")
      (node (ref "D1") (pin "1") (pinfunction "+_1") (pintype "passive"))
      (node (ref "R27") (pin "1") (pinfunction "1_1") (pintype "passive"))
    )
    (net (code "29") (name "Net-(D3-+)") (class "Default")
      (node (ref "D3") (pin "1") (pinfunction "+_1") (pintype "passive"))
      (node (ref "R33") (pin "1") (pinfunction "1_1") (pintype "passive"))
    )
    (net (code "30") (name "Net-(D3--)") (class "Default")
      (node (ref "C1") (pin "2") (pinfunction "2_2") (pintype "passive"))
      (node (ref "D3") (pin "2") (pinfunction "-_2") (pintype "passive"))
      (node (ref "IC5") (pin "2") (pinfunction "TR_2") (pintype "input"))
      (node (ref "IC5") (pin "6") (pinfunction "THR_6") (pintype "input"))
      (node (ref "R24") (pin "1") (pinfunction "1_1") (pintype "passive"))
      (node (ref "U$3") (pin "6") (pinfunction "D2_6") (pintype "passive"))
    )
    (net (code "31") (name "Net-(D5-PadC)") (class "Default")
      (node (ref "D5") (pin "C") (pinfunction "C_C") (pintype "passive"))
      (node (ref "R1") (pin "2") (pinfunction "2_2") (pintype "passive"))
      (node (ref "X1") (pin "22") (pinfunction "22_22") (pintype "passive"))
    )
    (net (code "32") (name "Net-(D8-+)") (class "Default")
      (node (ref "D8") (pin "1") (pinfunction "+_1") (pintype "passive"))
      (node (ref "R17") (pin "1") (pinfunction "1_1") (pintype "passive"))
    )
    (net (code "33") (name "Net-(D8--)") (class "Default")
      (node (ref "D8") (pin "2") (pinfunction "-_2") (pintype "passive"))
      (node (ref "IC7") (pin "2") (pinfunction "OUT_2") (pintype "open_collector"))
      (node (ref "Q10") (pin "1") (pinfunction "G_1") (pintype "passive"))
      (node (ref "R22") (pin "2") (pinfunction "2_2") (pintype "passive"))
      (node (ref "U$2") (pin "1") (pinfunction "1_1") (pintype "passive"))
    )
    (net (code "34") (name "Net-(D13-+)") (class "Default")
      (node (ref "D13") (pin "1") (pinfunction "+_1") (pintype "passive"))
      (node (ref "JP2") (pin "2") (pinfunction "2_2") (pintype "passive"))
    )
    (net (code "35") (name "Net-(D14-+)") (class "Default")
      (node (ref "D14") (pin "1") (pinfunction "+_1") (pintype "passive"))
      (node (ref "JP4") (pin "1") (pinfunction "1_1") (pintype "passive"))
    )
    (net (code "36") (name "Net-(D15--)") (class "Default")
      (node (ref "D15") (pin "2") (pinfunction "-_2") (pintype "passive"))
      (node (ref "Q1") (pin "2") (pinfunction "C_2") (pintype "passive"))
      (node (ref "START") (pin "TP") (pinfunction "PP_TP") (pintype "input"))
      (node (ref "X1") (pin "5") (pinfunction "5_5") (pintype "passive"))
    )
    (net (code "37") (name "Net-(IC3A-A)") (class "Default")
      (node (ref "IC3") (pin "10") (pinfunction "A_10") (pintype "input"))
      (node (ref "R31") (pin "1") (pinfunction "1_1") (pintype "passive"))
      (node (ref "U$3") (pin "1") (pinfunction "D1_1") (pintype "passive"))
      (node (ref "X1") (pin "4") (pinfunction "4_4") (pintype "passive"))
      (node (ref "X3") (pin "2") (pinfunction "S_2") (pintype "passive"))
    )
    (net (code "38") (name "Net-(IC3A-B)") (class "Default")
      (node (ref "IC3") (pin "13") (pinfunction "B_13") (pintype "input"))
      (node (ref "R30") (pin "1") (pinfunction "1_1") (pintype "passive"))
      (node (ref "U$3") (pin "4") (pinfunction "D4_4") (pintype "passive"))
      (node (ref "X1") (pin "3") (pinfunction "3_3") (pintype "passive"))
      (node (ref "X3") (pin "3") (pinfunction "S_3") (pintype "passive"))
    )
    (net (code "39") (name "Net-(IC3A-C)") (class "Default")
      (node (ref "IC3") (pin "12") (pinfunction "C_12") (pintype "input"))
      (node (ref "R29") (pin "1") (pinfunction "1_1") (pintype "passive"))
      (node (ref "U$3") (pin "3") (pinfunction "D3_3") (pintype "passive"))
      (node (ref "X1") (pin "2") (pinfunction "2_2") (pintype "passive"))
      (node (ref "X3") (pin "4") (pinfunction "S_4") (pintype "passive"))
    )
    (net (code "40") (name "Net-(IC3A-Q0)") (class "Default")
      (node (ref "IC3") (pin "3") (pinfunction "Q0_3") (pintype "output"))
      (node (ref "IC6") (pin "1") (pinfunction "I1_1") (pintype "input"))
      (node (ref "IC6") (pin "2") (pinfunction "I2_2") (pintype "input"))
      (node (ref "Q11") (pin "1") (pinfunction "G_1") (pintype "passive"))
    )
    (net (code "41") (name "Net-(IC3A-Q1)") (class "Default")
      (node (ref "IC3") (pin "14") (pinfunction "Q1_14") (pintype "output"))
      (node (ref "IC6") (pin "6") (pinfunction "I6_6") (pintype "input"))
    )
    (net (code "42") (name "Net-(IC3A-Q2)") (class "Default")
      (node (ref "IC3") (pin "2") (pinfunction "Q2_2") (pintype "output"))
      (node (ref "IC6") (pin "7") (pinfunction "I7_7") (pintype "input"))
    )
    (net (code "43") (name "Net-(IC3A-Q3)") (class "Default")
      (node (ref "IC3") (pin "15") (pinfunction "Q3_15") (pintype "output"))
      (node (ref "IC6") (pin "5") (pinfunction "I5_5") (pintype "input"))
    )
    (net (code "44") (name "Net-(IC3A-Q4)") (class "Default")
      (node (ref "IC3") (pin "1") (pinfunction "Q4_1") (pintype "output"))
      (node (ref "IC6") (pin "4") (pinfunction "I4_4") (pintype "input"))
    )
    (net (code "45") (name "Net-(IC3A-Q5)") (class "Default")
      (node (ref "IC3") (pin "6") (pinfunction "Q5_6") (pintype "output"))
      (node (ref "IC6") (pin "3") (pinfunction "I3_3") (pintype "input"))
    )
    (net (code "46") (name "Net-(IC4-ADJ)") (class "Default")
      (node (ref "IC4") (pin "1") (pinfunction "ADJ_1") (pintype "input"))
      (node (ref "R18") (pin "1") (pinfunction "1_1") (pintype "passive"))
      (node (ref "R5") (pin "2") (pinfunction "2_2") (pintype "passive"))
      (node (ref "X1") (pin "7") (pinfunction "7_7") (pintype "passive"))
    )
    (net (code "47") (name "Net-(IC4-VI)") (class "Default")
      (node (ref "IC4") (pin "3") (pinfunction "VI_3") (pintype "input"))
      (node (ref "Q2") (pin "2") (pinfunction "C_2") (pintype "passive"))
    )
    (net (code "48") (name "Net-(IC4-VO)") (class "Default")
      (node (ref "IC4") (pin "2") (pinfunction "VO_2") (pintype "passive"))
      (node (ref "R18") (pin "2") (pinfunction "2_2") (pintype "passive"))
    )
    (net (code "49") (name "Net-(IC5-CV)") (class "Default")
      (node (ref "IC5") (pin "5") (pinfunction "CV_5") (pintype "input"))
      (node (ref "R26") (pin "2") (pinfunction "2_2") (pintype "passive"))
    )
    (net (code "50") (name "Net-(IC5-Q)") (class "Default")
      (node (ref "IC5") (pin "3") (pinfunction "Q_3") (pintype "output"))
      (node (ref "IC8") (pin "12") (pinfunction "A_12") (pintype "input"))
      (node (ref "R26") (pin "1") (pinfunction "1_1") (pintype "passive"))
    )
    (net (code "51") (name "Net-(IC6-O1)") (class "Default")
      (node (ref "IC6") (pin "16") (pinfunction "O1_16") (pintype "open_collector"))
      (node (ref "Q9") (pin "2") (pinfunction "C_2") (pintype "passive"))
      (node (ref "R3") (pin "2") (pinfunction "2_2") (pintype "passive"))
      (node (ref "X1") (pin "21") (pinfunction "21_21") (pintype "passive"))
    )
    (net (code "52") (name "Net-(IC6-O2)") (class "Default")
      (node (ref "IC6") (pin "15") (pinfunction "O2_15") (pintype "open_collector"))
      (node (ref "R13") (pin "1") (pinfunction "1_1") (pintype "passive"))
    )
    (net (code "53") (name "Net-(IC7A-+IN)") (class "Default")
      (node (ref "IC7") (pin "5") (pinfunction "+IN_5") (pintype "input"))
      (node (ref "R15") (pin "1") (pinfunction "1_1") (pintype "passive"))
      (node (ref "R16") (pin "2") (pinfunction "2_2") (pintype "passive"))
      (node (ref "R17") (pin "2") (pinfunction "2_2") (pintype "passive"))
    )
    (net (code "54") (name "Net-(IC7A--IN)") (class "Default")
      (node (ref "C3") (pin "1") (pinfunction "1_1") (pintype "passive"))
      (node (ref "IC7") (pin "4") (pinfunction "-IN_4") (pintype "input"))
      (node (ref "R12") (pin "1") (pinfunction "1_1") (pintype "passive"))
    )
    (net (code "55") (name "Net-(IC7B-+IN)") (class "Default")
      (node (ref "IC7") (pin "7") (pinfunction "+IN_7") (pintype "input"))
      (node (ref "R25") (pin "1") (pinfunction "1_1") (pintype "passive"))
      (node (ref "R6") (pin "1") (pinfunction "1_1") (pintype "passive"))
    )
    (net (code "56") (name "Net-(IC7B--IN)") (class "Default")
      (node (ref "IC7") (pin "6") (pinfunction "-IN_6") (pintype "input"))
      (node (ref "IC7") (pin "8") (pinfunction "-IN_8") (pintype "input"))
      (node (ref "R5") (pin "1") (pinfunction "1_1") (pintype "passive"))
    )
    (net (code "57") (name "Net-(IC7B-OUT)") (class "Default")
      (node (ref "IC7") (pin "1") (pinfunction "OUT_1") (pintype "open_collector"))
      (node (ref "R10") (pin "2") (pinfunction "2_2") (pintype "passive"))
      (node (ref "R19") (pin "2") (pinfunction "2_2") (pintype "passive"))
    )
    (net (code "58") (name "Net-(IC7C-+IN)") (class "Default")
      (node (ref "C5") (pin "1") (pinfunction "1_1") (pintype "passive"))
      (node (ref "IC7") (pin "9") (pinfunction "+IN_9") (pintype "input"))
      (node (ref "R25") (pin "2") (pinfunction "2_2") (pintype "passive"))
      (node (ref "R8") (pin "2") (pinfunction "2_2") (pintype "passive"))
    )
    (net (code "59") (name "Net-(IC7C-OUT)") (class "Default")
      (node (ref "C9") (pin "2") (pinfunction "2_2") (pintype "passive"))
      (node (ref "IC7") (pin "14") (pinfunction "OUT_14") (pintype "open_collector"))
      (node (ref "R9") (pin "2") (pinfunction "2_2") (pintype "passive"))
    )
    (net (code "60") (name "Net-(IC8B-B)") (class "Default")
      (node (ref "IC8") (pin "11") (pinfunction "B_11") (pintype "input"))
      (node (ref "IC8") (pin "9") (pinfunction "~{Q}_9") (pintype "output"))
      (node (ref "R35") (pin "2") (pinfunction "2_2") (pintype "passive"))
    )
    (net (code "61") (name "Net-(IC8B-T2)") (class "Default")
      (node (ref "C10") (pin "1") (pinfunction "1_1") (pintype "passive"))
      (node (ref "IC8") (pin "14") (pinfunction "T2_14") (pintype "input"))
      (node (ref "R34") (pin "1") (pinfunction "1_1") (pintype "passive"))
    )
    (net (code "62") (name "Net-(IC10A-+IN)") (class "Default")
      (node (ref "C8") (pin "1") (pinfunction "1_1") (pintype "passive"))
      (node (ref "IC10") (pin "3") (pinfunction "+IN_3") (pintype "input"))
      (node (ref "R1") (pin "1") (pinfunction "1_1") (pintype "passive"))
    )
    (net (code "63") (name "Net-(IC10A--IN)") (class "Default")
      (node (ref "IC10") (pin "2") (pinfunction "-IN_2") (pintype "input"))
      (node (ref "R2") (pin "2") (pinfunction "2_2") (pintype "passive"))
    )
    (net (code "64") (name "Net-(IC10A-OUT)") (class "Default")
      (node (ref "IC10") (pin "1") (pinfunction "OUT_1") (pintype "output"))
      (node (ref "R42") (pin "2") (pinfunction "2_2") (pintype "passive"))
    )
    (net (code "65") (name "Net-(IC10B-+IN)") (class "Default")
      (node (ref "IC10") (pin "5") (pinfunction "+IN_5") (pintype "input"))
      (node (ref "R43") (pin "2") (pinfunction "2_2") (pintype "passive"))
      (node (ref "R44") (pin "2") (pinfunction "2_2") (pintype "passive"))
    )
    (net (code "66") (name "Net-(IC10B--IN)") (class "Default")
      (node (ref "IC10") (pin "6") (pinfunction "-IN_6") (pintype "input"))
      (node (ref "R45") (pin "1") (pinfunction "1_1") (pintype "passive"))
      (node (ref "R46") (pin "2") (pinfunction "2_2") (pintype "passive"))
    )
    (net (code "67") (name "Net-(IC10B-OUT)") (class "Default")
      (node (ref "IC10") (pin "7") (pinfunction "OUT_7") (pintype "output"))
      (node (ref "R32") (pin "1") (pinfunction "1_1") (pintype "passive"))
      (node (ref "R44") (pin "1") (pinfunction "1_1") (pintype "passive"))
    )
    (net (code "68") (name "Net-(JP1-Pad2)") (class "Default")
      (node (ref "JP1") (pin "2") (pinfunction "2_2") (pintype "passive"))
      (node (ref "R36") (pin "2") (pinfunction "2_2") (pintype "passive"))
      (node (ref "R37") (pin "2") (pinfunction "2_2") (pintype "passive"))
      (node (ref "SJ1") (pin "2") (pinfunction "2_2") (pintype "passive"))
    )
    (net (code "69") (name "Net-(JP3-Pad1)") (class "Default")
      (node (ref "JP3") (pin "1") (pinfunction "1_1") (pintype "passive"))
      (node (ref "R23") (pin "2") (pinfunction "2_2") (pintype "passive"))
    )
    (net (code "70") (name "Net-(LED1-PadA)") (class "Default")
      (node (ref "LED1") (pin "A") (pinfunction "A_A") (pintype "passive"))
      (node (ref "LED2") (pin "A") (pinfunction "A_A") (pintype "passive"))
      (node (ref "LED3") (pin "A") (pinfunction "A_A") (pintype "passive"))
      (node (ref "LED4") (pin "A") (pinfunction "A_A") (pintype "passive"))
      (node (ref "LED7") (pin "A") (pinfunction "A_A") (pintype "passive"))
      (node (ref "R11") (pin "1") (pinfunction "1_1") (pintype "passive"))
    )
    (net (code "71") (name "Net-(LED6-C)") (class "Default")
      (node (ref "LED6") (pin "K") (pinfunction "C_K") (pintype "passive"))
      (node (ref "R4") (pin "1") (pinfunction "1_1") (pintype "passive"))
    )
    (net (code "72") (name "Net-(Q1-B)") (class "Default")
      (node (ref "Q1") (pin "1") (pinfunction "B_1") (pintype "passive"))
      (node (ref "R13") (pin "2") (pinfunction "2_2") (pintype "passive"))
    )
    (net (code "73") (name "Net-(Q2-B)") (class "Default")
      (node (ref "Q2") (pin "1") (pinfunction "B_1") (pintype "passive"))
      (node (ref "R9") (pin "1") (pinfunction "1_1") (pintype "passive"))
    )
    (net (code "74") (name "Net-(Q7-B)") (class "Default")
      (node (ref "Q7") (pin "1") (pinfunction "B_1") (pintype "passive"))
      (node (ref "Q7") (pin "2") (pinfunction "C_2") (pintype "passive"))
      (node (ref "Q8") (pin "1") (pinfunction "B_1") (pintype "passive"))
      (node (ref "R38") (pin "1") (pinfunction "1_1") (pintype "passive"))
      (node (ref "R39") (pin "1") (pinfunction "1_1") (pintype "passive"))
      (node (ref "X2") (pin "2") (pinfunction "S_2") (pintype "passive"))
    )
    (net (code "75") (name "Net-(Q7-E)") (class "Default")
      (node (ref "Q7") (pin "3") (pinfunction "E_3") (pintype "passive"))
      (node (ref "R20") (pin "2") (pinfunction "2_2") (pintype "passive"))
    )
    (net (code "76") (name "Net-(Q8-E)") (class "Default")
      (node (ref "Q8") (pin "3") (pinfunction "E_3") (pintype "passive"))
      (node (ref "R21") (pin "2") (pinfunction "2_2") (pintype "passive"))
    )
    (net (code "77") (name "Net-(Q9-B)") (class "Default")
      (node (ref "Q9") (pin "1") (pinfunction "B_1") (pintype "passive"))
      (node (ref "R32") (pin "2") (pinfunction "2_2") (pintype "passive"))
    )
    (net (code "78") (name "Net-(Q10-D)") (class "Default")
      (node (ref "Q10") (pin "3") (pinfunction "D_3") (pintype "passive"))
      (node (ref "R7") (pin "2") (pinfunction "2_2") (pintype "passive"))
    )
    (net (code "79") (name "Net-(R14-Pad1)") (class "Default")
      (node (ref "R14") (pin "1") (pinfunction "1_1") (pintype "passive"))
      (node (ref "R7") (pin "1") (pinfunction "1_1") (pintype "passive"))
      (node (ref "U$2") (pin "3") (pinfunction "3_3") (pintype "passive"))
    )
    (net (code "80") (name "Net-(R27-Pad2)") (class "Default")
      (node (ref "R27") (pin "2") (pinfunction "2_2") (pintype "passive"))
      (node (ref "R28") (pin "1") (pinfunction "1_1") (pintype "passive"))
    )
    (net (code "81") (name "Net-(R33-Pad2)") (class "Default")
      (node (ref "R33") (pin "2") (pinfunction "2_2") (pintype "passive"))
      (node (ref "X1") (pin "16") (pinfunction "16_16") (pintype "passive"))
    )
    (net (code "82") (name "VCC") (class "Default")
      (node (ref "6V") (pin "TP") (pinfunction "PP_TP") (pintype "input"))
      (node (ref "C4") (pin "1") (pinfunction "1_1") (pintype "passive"))
      (node (ref "IC1") (pin "OUT") (pinfunction "OUT_OUT") (pintype "passive"))
      (node (ref "IC10") (pin "8") (pinfunction "V+_8") (pintype "power_in"))
      (node (ref "IC2") (pin "1") (pinfunction "OUT_1") (pintype "passive"))
      (node (ref "IC7") (pin "3") (pinfunction "V+_3") (pintype "power_in"))
      (node (ref "R11") (pin "2") (pinfunction "2_2") (pintype "passive"))
      (node (ref "R15") (pin "2") (pinfunction "2_2") (pintype "passive"))
      (node (ref "R19") (pin "1") (pinfunction "1_1") (pintype "passive"))
      (node (ref "R45") (pin "2") (pinfunction "2_2") (pintype "passive"))
      (node (ref "R6") (pin "2") (pinfunction "2_2") (pintype "passive"))
    )
    (net (code "83") (name "unconnected-(IC3A-Q6-Pad7)") (class "Default")
      (node (ref "IC3") (pin "7") (pinfunction "Q6_7") (pintype "output"))
    )
    (net (code "84") (name "unconnected-(IC3A-Q7-Pad4)") (class "Default")
      (node (ref "IC3") (pin "4") (pinfunction "Q7_4") (pintype "output"))
    )
    (net (code "85") (name "unconnected-(IC3A-Q8-Pad9)") (class "Default")
      (node (ref "IC3") (pin "9") (pinfunction "Q8_9") (pintype "output"))
    )
    (net (code "86") (name "unconnected-(IC3A-Q9-Pad5)") (class "Default")
      (node (ref "IC3") (pin "5") (pinfunction "Q9_5") (pintype "output"))
    )
    (net (code "87") (name "unconnected-(IC5-DIS-Pad7)") (class "Default")
      (node (ref "IC5") (pin "7") (pinfunction "DIS_7") (pintype "input"))
    )
    (net (code "88") (name "unconnected-(IC7D-OUT-Pad13)") (class "Default")
      (node (ref "IC7") (pin "13") (pinfunction "OUT_13") (pintype "open_collector"))
    )
    (net (code "89") (name "unconnected-(IC8A-Q-Pad6)") (class "Default")
      (node (ref "IC8") (pin "6") (pinfunction "Q_6") (pintype "output"))
    )
    (net (code "90") (name "unconnected-(IC8A-T2-Pad2)") (class "Default")
      (node (ref "IC8") (pin "2") (pinfunction "T2_2") (pintype "input"))
    )
    (net (code "91") (name "unconnected-(IC8A-~{Q}-Pad7)") (class "Default")
      (node (ref "IC8") (pin "7") (pinfunction "~{Q}_7") (pintype "output"))
    )
    (net (code "92") (name "unconnected-(IC8B-Q-Pad10)") (class "Default")
      (node (ref "IC8") (pin "10") (pinfunction "Q_10") (pintype "output"))
    )
    (net (code "93") (name "unconnected-(X1-Pad20)") (class "Default")
      (node (ref "X1") (pin "20") (pinfunction "20_20") (pintype "passive"))
    )
    (net (code "94") (name "unconnected-(X1-Pad24)") (class "Default")
      (node (ref "X1") (pin "24") (pinfunction "24_24") (pintype "passive"))
    )
  )
)
